# design.net
KiCad netlist of a schematic drawn in Altium Designer
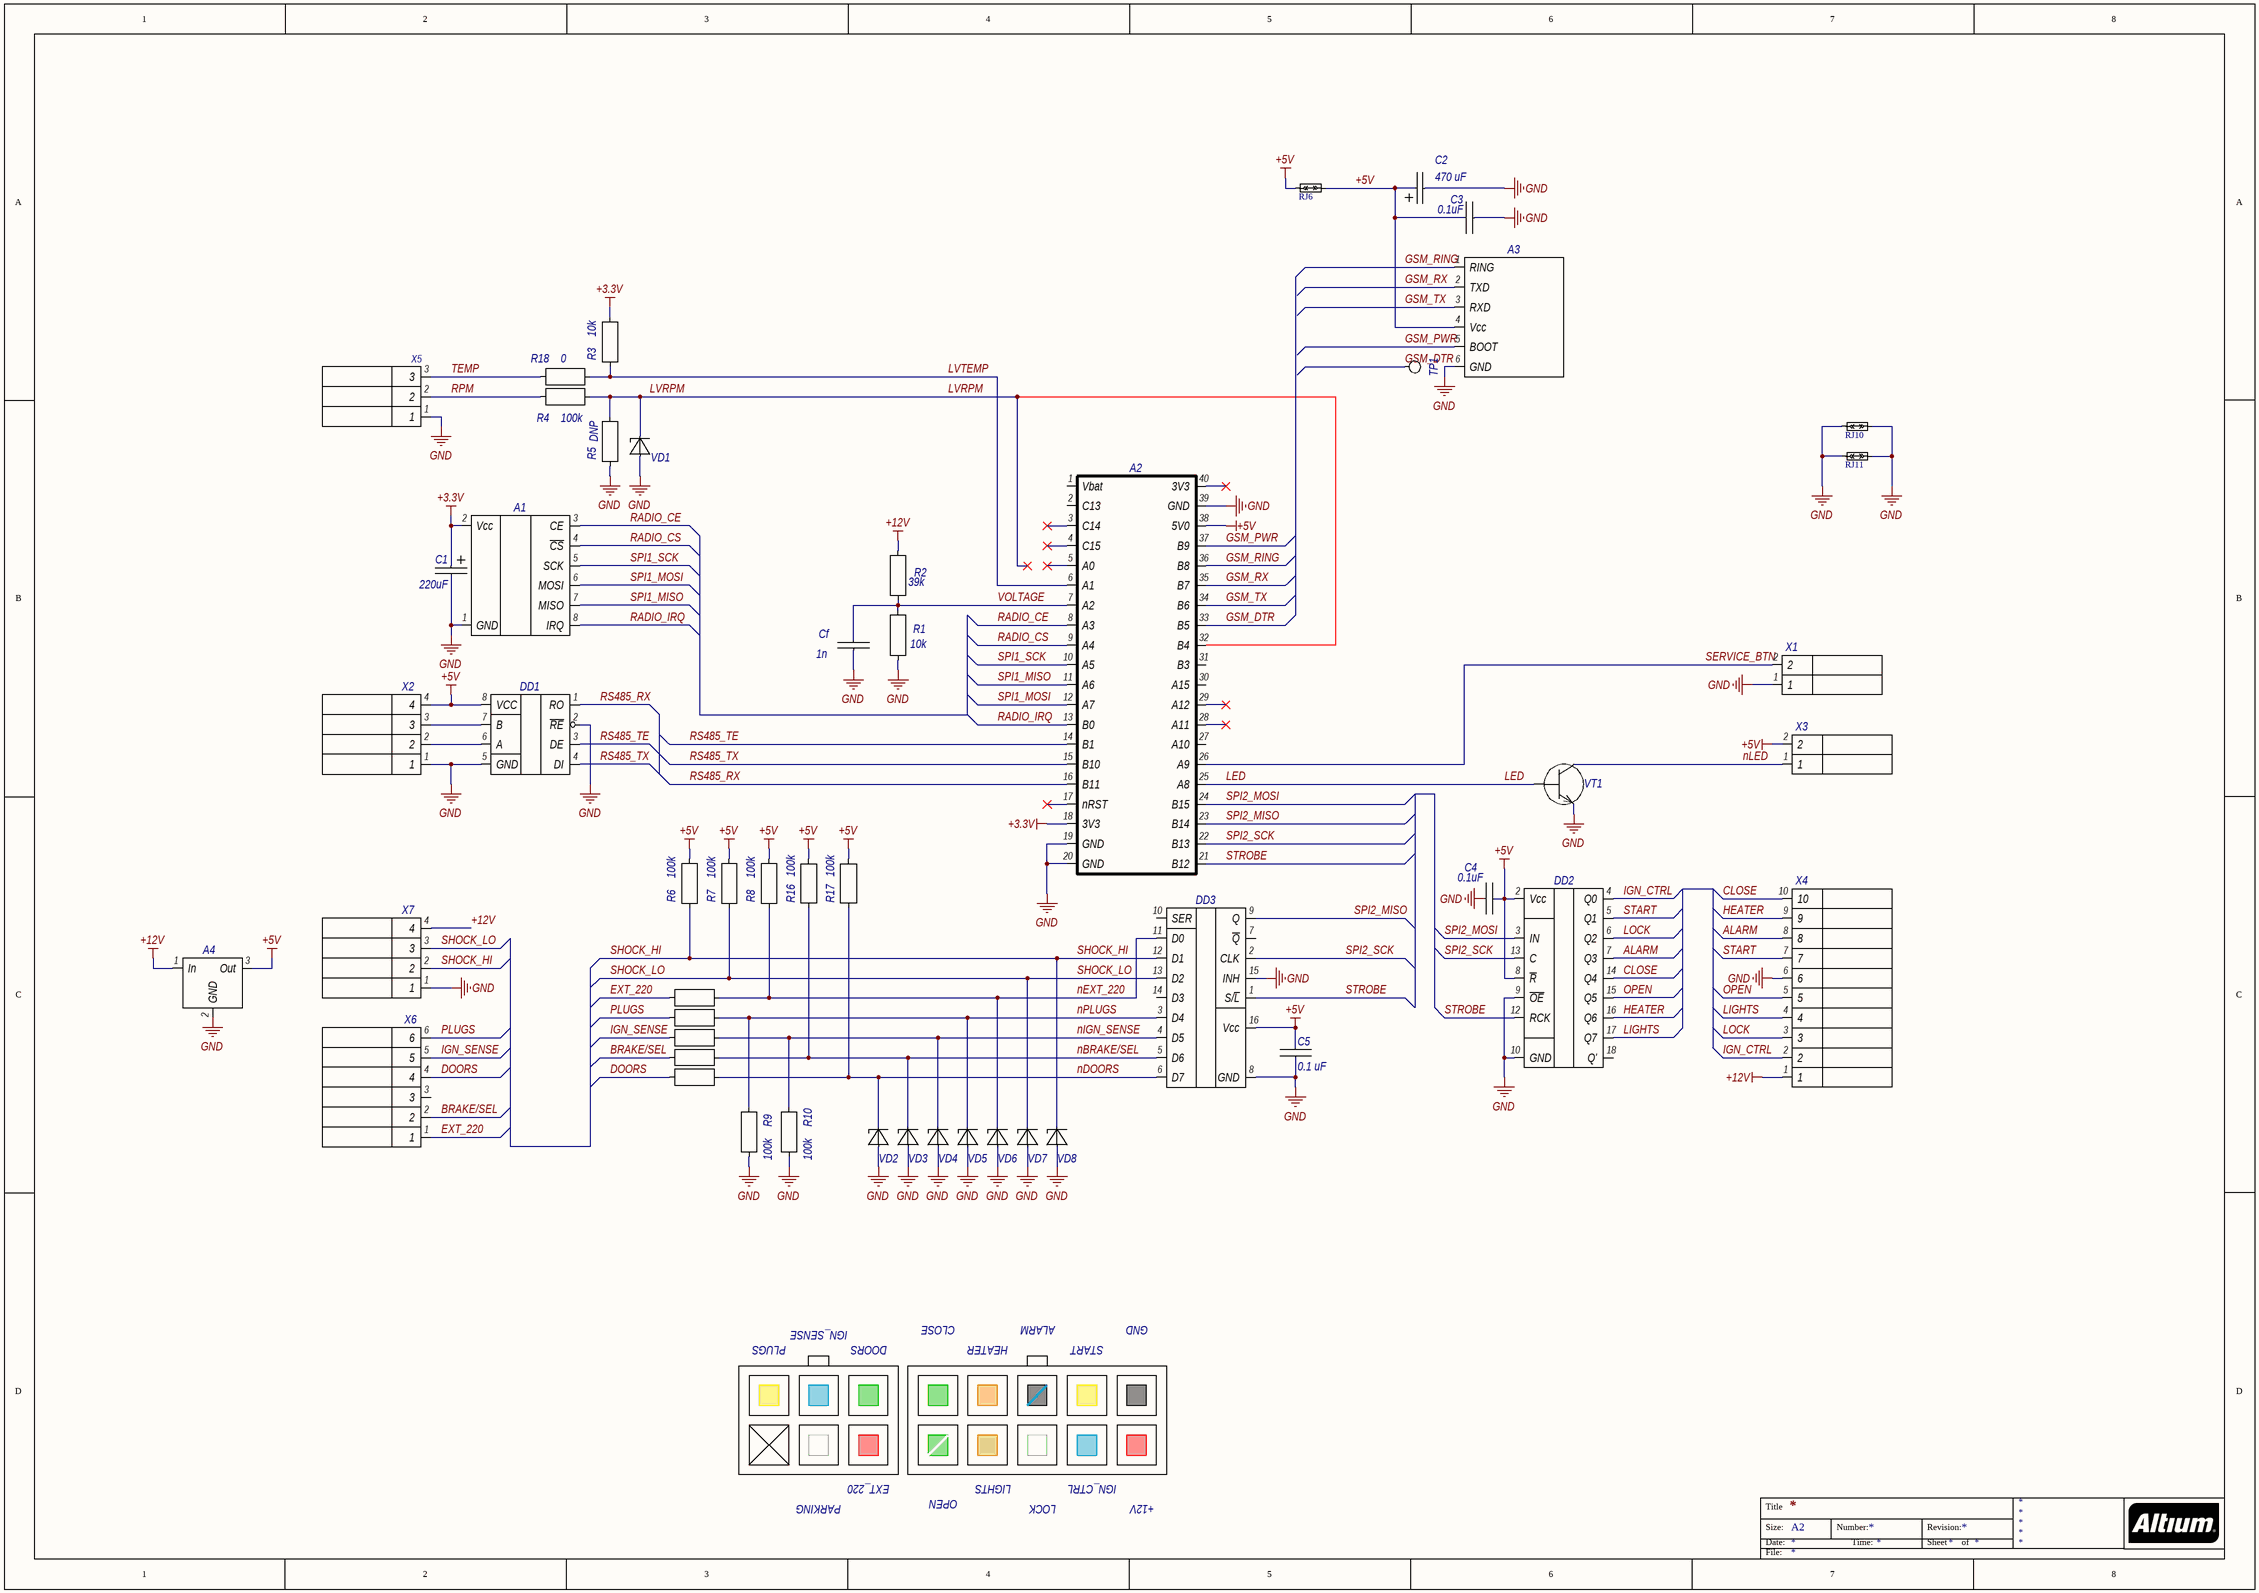
[diagram p0: Основной блок.SchDoc]

(export (version "E")
  (design (tool "Eeschema 10.0.6"))
  (components
    (comp (ref "A1")
      (value "nRF24L01 + PA + LNA")
      (footprint "nRF24L01+PA+LNA Thruhole")
      (description "=PartNumber")
      (fields (field (name "PARTNUMBER") "nRF24L01+PA+LNA Module"))
      (libsource (lib "modules") (part "nRF24L01 + PA + LNA"))
    )
    (comp (ref "A2")
      (value "STM32-1")
      (footprint "STM32 Module No. 1")
      (description "=PartNumber")
      (fields (field (name "PARTNUMBER") "STM32F103 \"Blue Pill\" Module"))
      (libsource (lib "modules") (part "STM32-1"))
    )
    (comp (ref "A3")
      (value "M590E Сборка")
      (footprint "M590E_Module_1")
      (description "=PartNumber")
      (fields (field (name "PARTNUMBER") "Neoway M590 Assy"))
      (libsource (lib "modules") (part "M590E Сборка"))
    )
    (comp (ref "A4")
      (value "LM2596 Module")
      (footprint "LM2596 Module")
      (description "=PartNumber")
      (fields (field (name "PARTNUMBER") "DC-DC Converter Module"))
      (libsource (lib "modules") (part "LM2596 Module"))
    )
    (comp (ref "C1")
      (value "220uF")
      (footprint "CAP_TYPE_C")
      (description "=PartNumber")
      (fields (field (name "PARTNUMBER") "T491C227K006AT") (field (name "Comment") "Конденсатор"))
      (libsource (lib "RCL") (part "Конденсатор"))
    )
    (comp (ref "C2")
      (value "470 uF")
      (footprint "CAP_TYPE_D")
      (description "=PartNumber")
      (fields (field (name "PARTNUMBER") "T491D477K006AT") (field (name "Comment") "Конденсатор"))
      (libsource (lib "RCL") (part "Конденсатор"))
    )
    (comp (ref "C3")
      (value "0.1uF")
      (footprint "CHIP_0603_C")
      (description "=PartNumber")
      (fields (field (name "PARTNUMBER") "CC0603KRX7R7BB104") (field (name "Comment") "Конденсатор"))
      (libsource (lib "") (part "Конденсатор_1"))
    )
    (comp (ref "C4")
      (value "0.1uF")
      (footprint "CHIP_0603_C")
      (description "=PartNumber")
      (fields (field (name "PARTNUMBER") "CC0603KRX7R7BB104") (field (name "Comment") "Конденсатор"))
      (libsource (lib "") (part "Конденсатор_1"))
    )
    (comp (ref "C5")
      (value "0.1 uF")
      (footprint "CHIP_1206_C")
      (description "=PartNumber")
      (fields (field (name "PARTNUMBER") "CC1206KRX7R9BB104") (field (name "Comment") "Конденсатор"))
      (libsource (lib "") (part "Конденсатор_1"))
    )
    (comp (ref "Cf")
      (value "1n")
      (footprint "CHIP_0603_C")
      (description "=PartNumber")
      (fields (field (name "PARTNUMBER") "CC0603KRX7R7BB104") (field (name "Comment") "Конденсатор"))
      (libsource (lib "") (part "Конденсатор_1"))
    )
    (comp (ref "DD1")
      (value "ADM485AR")
      (footprint "SO8")
      (description "=PartNumber")
      (fields (field (name "PARTNUMBER") "ADM485ARZ-REEL"))
      (libsource (lib "ic") (part "ADM485AR"))
    )
    (comp (ref "DD2")
      (value "TPIC6B595")
      (footprint "SO20W - TPIC6B595")
      (description "=PartNumber")
      (fields (field (name "PARTNUMBER") "TPIC6B595DW (SO20W)"))
      (libsource (lib "ic") (part "TPIC6B595"))
    )
    (comp (ref "DD3")
      (value "74HC165")
      (footprint "DIP16")
      (description "=PartNumber")
      (fields (field (name "PARTNUMBER") "SN74HC165N  (DIP16)"))
      (libsource (lib "ic") (part "74HC165"))
    )
    (comp (ref "R1")
      (value "10k")
      (footprint "CHIP_0603_R")
      (description "=PartNumber")
      (fields (field (name "Comment") "Резистор"))
      (libsource (lib "RCL") (part "Резистор"))
    )
    (comp (ref "R2")
      (value "39k")
      (footprint "R_0.125 - 400mil")
      (description "=PartNumber")
      (fields (field (name "Comment") "Резистор"))
      (libsource (lib "RCL") (part "Резистор"))
    )
    (comp (ref "R3")
      (value "10k")
      (footprint "CHIP_0603_R")
      (description "=PartNumber")
      (fields (field (name "Comment") "Резистор"))
      (libsource (lib "RCL") (part "Резистор"))
    )
    (comp (ref "R4")
      (value "100k")
      (footprint "CHIP_1206_R")
      (description "=PartNumber")
      (fields (field (name "Comment") "Резистор"))
      (libsource (lib "RCL") (part "Резистор"))
    )
    (comp (ref "R5")
      (value "DNP")
      (footprint "CHIP_0603_R")
      (description "=PartNumber")
      (fields (field (name "Comment") "Резистор"))
      (libsource (lib "RCL") (part "Резистор"))
    )
    (comp (ref "R6")
      (value "100k")
      (footprint "CHIP_1206_R")
      (description "=PartNumber")
      (fields (field (name "PARTNUMBER") "RC1206FR-07100KL") (field (name "Comment") "Резистор"))
      (libsource (lib "RCL") (part "Резистор"))
    )
    (comp (ref "R7")
      (value "100k")
      (footprint "CHIP_1206_R")
      (description "=PartNumber")
      (fields (field (name "PARTNUMBER") "RC1206FR-07100KL") (field (name "Comment") "Резистор"))
      (libsource (lib "RCL") (part "Резистор"))
    )
    (comp (ref "R8")
      (value "100k")
      (footprint "CHIP_1206_R")
      (description "=PartNumber")
      (fields (field (name "PARTNUMBER") "RC1206FR-07100KL") (field (name "Comment") "Резистор"))
      (libsource (lib "RCL") (part "Резистор"))
    )
    (comp (ref "R9")
      (value "100k")
      (footprint "CHIP_1206_R")
      (description "=PartNumber")
      (fields (field (name "PARTNUMBER") "RC1206FR-07100KL") (field (name "Comment") "Резистор"))
      (libsource (lib "RCL") (part "Резистор"))
    )
    (comp (ref "R10")
      (value "100k")
      (footprint "CHIP_1206_R")
      (description "=PartNumber")
      (fields (field (name "PARTNUMBER") "RC1206FR-07100KL") (field (name "Comment") "Резистор"))
      (libsource (lib "RCL") (part "Резистор"))
    )
    (comp (ref "R11")
      (value "Резистор")
      (footprint "R_0.125 - 400mil")
      (description "=PartNumber")
      (libsource (lib "RCL") (part "Резистор"))
    )
    (comp (ref "R12")
      (value "Резистор")
      (footprint "R_0.125 - 400mil")
      (description "=PartNumber")
      (libsource (lib "RCL") (part "Резистор"))
    )
    (comp (ref "R13")
      (value "Резистор")
      (footprint "R_0.125 - 400mil")
      (description "=PartNumber")
      (libsource (lib "RCL") (part "Резистор"))
    )
    (comp (ref "R14")
      (value "Резистор")
      (footprint "R_0.125 - 400mil")
      (description "=PartNumber")
      (libsource (lib "RCL") (part "Резистор"))
    )
    (comp (ref "R15")
      (value "Резистор")
      (footprint "R_0.125 - 400mil")
      (description "=PartNumber")
      (libsource (lib "RCL") (part "Резистор"))
    )
    (comp (ref "R16")
      (value "100k")
      (footprint "CHIP_1206_R")
      (description "=PartNumber")
      (fields (field (name "PARTNUMBER") "RC1206FR-07100KL") (field (name "Comment") "Резистор"))
      (libsource (lib "RCL") (part "Резистор"))
    )
    (comp (ref "R17")
      (value "100k")
      (footprint "CHIP_1206_R")
      (description "=PartNumber")
      (fields (field (name "PARTNUMBER") "RC1206FR-07100KL") (field (name "Comment") "Резистор"))
      (libsource (lib "RCL") (part "Резистор"))
    )
    (comp (ref "R18")
      (value "0")
      (footprint "CHIP_1206_R")
      (description "=PartNumber")
      (fields (field (name "Comment") "Резистор"))
      (libsource (lib "RCL") (part "Резистор"))
    )
    (comp (ref "RJ6")
      (value "R0")
      (footprint "CHIP_1206_R0")
      (description "=PartNumber")
      (fields (field (name "PARTNUMBER") "RC1206JR-070RL"))
      (libsource (lib "passive") (part "R0"))
    )
    (comp (ref "RJ10")
      (value "R0")
      (footprint "CHIP_1206_R0")
      (description "=PartNumber")
      (fields (field (name "PARTNUMBER") "RC1206JR-070RL"))
      (libsource (lib "passive") (part "R0"))
    )
    (comp (ref "RJ11")
      (value "R0")
      (footprint "CHIP_1206_R0")
      (description "=PartNumber")
      (fields (field (name "PARTNUMBER") "RC1206JR-070RL"))
      (libsource (lib "passive") (part "R0"))
    )
    (comp (ref "TP1")
      (value "TEST_POINT")
      (footprint "Mounting hole 1.5mm")
      (libsource (lib "conn") (part "TEST_POINT"))
    )
    (comp (ref "VD1")
      (value "Zener")
      (footprint "SOD-80")
      (description "=PartNumber")
      (fields (field (name "PARTNUMBER") "ZMM5226B (ZMM55C-3V3)"))
      (libsource (lib "Semiconductors") (part "Zener"))
    )
    (comp (ref "VD2")
      (value "Zener")
      (footprint "SOD-80")
      (description "=PartNumber")
      (fields (field (name "PARTNUMBER") "ZMM5229B (ZMM55C-4V3)"))
      (libsource (lib "Semiconductors") (part "Zener"))
    )
    (comp (ref "VD3")
      (value "Zener")
      (footprint "SOD-80")
      (description "=PartNumber")
      (fields (field (name "PARTNUMBER") "ZMM5229B (ZMM55C-4V3)"))
      (libsource (lib "Semiconductors") (part "Zener"))
    )
    (comp (ref "VD4")
      (value "Zener")
      (footprint "SOD-80")
      (description "=PartNumber")
      (fields (field (name "PARTNUMBER") "ZMM5229B (ZMM55C-4V3)"))
      (libsource (lib "Semiconductors") (part "Zener"))
    )
    (comp (ref "VD5")
      (value "Zener")
      (footprint "SOD-80")
      (description "=PartNumber")
      (fields (field (name "PARTNUMBER") "ZMM5229B (ZMM55C-4V3)"))
      (libsource (lib "Semiconductors") (part "Zener"))
    )
    (comp (ref "VD6")
      (value "Zener")
      (footprint "SOD-80")
      (description "=PartNumber")
      (fields (field (name "PARTNUMBER") "ZMM5229B (ZMM55C-4V3)"))
      (libsource (lib "Semiconductors") (part "Zener"))
    )
    (comp (ref "VD7")
      (value "Zener")
      (footprint "SOD-80")
      (description "=PartNumber")
      (fields (field (name "PARTNUMBER") "ZMM5229B (ZMM55C-4V3)"))
      (libsource (lib "Semiconductors") (part "Zener"))
    )
    (comp (ref "VD8")
      (value "Zener")
      (footprint "SOD-80")
      (description "=PartNumber")
      (fields (field (name "PARTNUMBER") "ZMM5229B (ZMM55C-4V3)"))
      (libsource (lib "Semiconductors") (part "Zener"))
    )
    (comp (ref "VT1")
      (value "BJT, NPN")
      (footprint "SOT-23")
      (description "=PartNumber")
      (fields (field (name "PARTNUMBER") "KSR1002") (field (name "MFG") "SAM"))
      (libsource (lib "Semiconductors") (part "BJT, NPN"))
    )
    (comp (ref "X1")
      (value "PH-02M(R)")
      (footprint "PH-02MR")
      (description "=PartNumber")
      (fields (field (name "PARTNUMBER") "PH 02MR 2.0mm"))
      (libsource (lib "conn") (part "PH-02M(R)"))
    )
    (comp (ref "X2")
      (value "PH-04M(R)")
      (footprint "PH-04M")
      (description "=PartNumber")
      (fields (field (name "PARTNUMBER") "PH 02M 2.0mm"))
      (libsource (lib "conn") (part "PH-04M(R)"))
    )
    (comp (ref "X3")
      (value "PH-02M(R)")
      (footprint "PH-02MR")
      (description "=PartNumber")
      (fields (field (name "PARTNUMBER") "PH 02MR 2.0mm"))
      (libsource (lib "conn") (part "PH-02M(R)"))
    )
    (comp (ref "X4")
      (value "MF 2x05 M(R)")
      (footprint "MF 2x05 R")
      (description "=PartNumber")
      (fields (field (name "PARTNUMBER") "MF 2x05MR"))
      (libsource (lib "conn") (part "MF 2x05 M(R)"))
    )
    (comp (ref "X5")
      (value "PH-03M(R)")
      (footprint "PH-03M")
      (description "=PartNumber")
      (fields (field (name "PARTNUMBER") "PH 02M 2.0mm"))
      (libsource (lib "conn") (part "PH-03M(R)"))
    )
    (comp (ref "X6")
      (value "MF 2x03 M(R)")
      (footprint "MF 2x03 R")
      (description "=PartNumber")
      (fields (field (name "PARTNUMBER") "MF 2x03MR"))
      (libsource (lib "conn") (part "MF 2x03 M(R)"))
    )
    (comp (ref "X7")
      (value "PH-04M(R)")
      (footprint "PH-04MR")
      (description "=PartNumber")
      (fields (field (name "PARTNUMBER") "PH 04MR 2.0mm"))
      (libsource (lib "conn") (part "PH-04M(R)"))
    )
  )
  (nets
    (net (code "1") (name "+3.3V") (class "Default")
      (node (ref "A1") (pin "2") (pinfunction "Vcc_2") (pintype "passive"))
      (node (ref "A2") (pin "18") (pinfunction "3V3_18") (pintype "passive"))
      (node (ref "C1") (pin "2") (pinfunction "2_2") (pintype "passive"))
      (node (ref "R3") (pin "2") (pinfunction "2_2") (pintype "passive"))
    )
    (net (code "2") (name "+5V") (class "Default")
      (node (ref "A2") (pin "38") (pinfunction "5V0_38") (pintype "passive"))
      (node (ref "A3") (pin "4") (pinfunction "Vcc_4") (pintype "passive"))
      (node (ref "A4") (pin "3") (pinfunction "Out_3") (pintype "passive"))
      (node (ref "C2") (pin "2") (pinfunction "2_2") (pintype "passive"))
      (node (ref "C3") (pin "1") (pinfunction "1_1") (pintype "passive"))
      (node (ref "C4") (pin "1") (pinfunction "1_1") (pintype "passive"))
      (node (ref "C5") (pin "2") (pinfunction "2_2") (pintype "passive"))
      (node (ref "DD1") (pin "8") (pinfunction "VCC_8") (pintype "passive"))
      (node (ref "DD2") (pin "2") (pinfunction "Vcc_2") (pintype "passive"))
      (node (ref "DD2") (pin "8") (pinfunction "R_8") (pintype "passive"))
      (node (ref "DD3") (pin "16") (pinfunction "Vcc_16") (pintype "passive"))
      (node (ref "R16") (pin "1") (pinfunction "1_1") (pintype "passive"))
      (node (ref "R17") (pin "1") (pinfunction "1_1") (pintype "passive"))
      (node (ref "R6") (pin "2") (pinfunction "2_2") (pintype "passive"))
      (node (ref "R7") (pin "2") (pinfunction "2_2") (pintype "passive"))
      (node (ref "R8") (pin "2") (pinfunction "2_2") (pintype "passive"))
      (node (ref "RJ6") (pin "1") (pinfunction "1_1") (pintype "passive"))
      (node (ref "RJ6") (pin "2") (pinfunction "2_2") (pintype "passive"))
      (node (ref "X2") (pin "4") (pinfunction "4_4") (pintype "passive"))
      (node (ref "X3") (pin "2") (pinfunction "2_2") (pintype "passive"))
    )
    (net (code "3") (name "+12V") (class "Default")
      (node (ref "A4") (pin "1") (pinfunction "In_1") (pintype "passive"))
      (node (ref "R2") (pin "2") (pinfunction "2_2") (pintype "passive"))
      (node (ref "X4") (pin "1") (pinfunction "1_1") (pintype "passive"))
      (node (ref "X7") (pin "4") (pinfunction "4_4") (pintype "passive"))
    )
    (net (code "4") (name "/ALARM") (class "Default")
      (node (ref "DD2") (pin "7") (pinfunction "Q3_7") (pintype "passive"))
      (node (ref "X4") (pin "8") (pinfunction "8_8") (pintype "passive"))
    )
    (net (code "5") (name "/BRAKE{slash}SEL") (class "Default")
      (node (ref "R14") (pin "1") (pinfunction "1_1") (pintype "passive"))
      (node (ref "X6") (pin "2") (pinfunction "2_2") (pintype "passive"))
    )
    (net (code "6") (name "/CLOSE") (class "Default")
      (node (ref "DD2") (pin "14") (pinfunction "Q4_14") (pintype "passive"))
      (node (ref "X4") (pin "10") (pinfunction "10_10") (pintype "passive"))
    )
    (net (code "7") (name "/DOORS") (class "Default")
      (node (ref "R15") (pin "1") (pinfunction "1_1") (pintype "passive"))
      (node (ref "X6") (pin "4") (pinfunction "4_4") (pintype "passive"))
    )
    (net (code "8") (name "/EXT_220") (class "Default")
      (node (ref "R11") (pin "1") (pinfunction "1_1") (pintype "passive"))
      (node (ref "X6") (pin "1") (pinfunction "1_1") (pintype "passive"))
    )
    (net (code "9") (name "/GSM_DTR") (class "Default")
      (node (ref "A2") (pin "33") (pinfunction "B5_33") (pintype "passive"))
      (node (ref "TP1") (pin "1") (pintype "passive"))
    )
    (net (code "10") (name "/GSM_PWR") (class "Default")
      (node (ref "A2") (pin "37") (pinfunction "B9_37") (pintype "passive"))
      (node (ref "A3") (pin "5") (pinfunction "BOOT_5") (pintype "passive"))
    )
    (net (code "11") (name "/GSM_RING") (class "Default")
      (node (ref "A2") (pin "36") (pinfunction "B8_36") (pintype "passive"))
      (node (ref "A3") (pin "1") (pinfunction "RING_1") (pintype "passive"))
    )
    (net (code "12") (name "/GSM_RX") (class "Default")
      (node (ref "A2") (pin "35") (pinfunction "B7_35") (pintype "passive"))
      (node (ref "A3") (pin "2") (pinfunction "TXD_2") (pintype "passive"))
    )
    (net (code "13") (name "/GSM_TX") (class "Default")
      (node (ref "A2") (pin "34") (pinfunction "B6_34") (pintype "passive"))
      (node (ref "A3") (pin "3") (pinfunction "RXD_3") (pintype "passive"))
    )
    (net (code "14") (name "/HEATER") (class "Default")
      (node (ref "DD2") (pin "16") (pinfunction "Q6_16") (pintype "passive"))
      (node (ref "X4") (pin "9") (pinfunction "9_9") (pintype "passive"))
    )
    (net (code "15") (name "/IGN_CTRL") (class "Default")
      (node (ref "DD2") (pin "4") (pinfunction "Q0_4") (pintype "passive"))
      (node (ref "X4") (pin "2") (pinfunction "2_2") (pintype "passive"))
    )
    (net (code "16") (name "/IGN_SENSE") (class "Default")
      (node (ref "R13") (pin "1") (pinfunction "1_1") (pintype "passive"))
      (node (ref "X6") (pin "5") (pinfunction "5_5") (pintype "passive"))
    )
    (net (code "17") (name "/LED") (class "Default")
      (node (ref "A2") (pin "25") (pinfunction "A8_25") (pintype "passive"))
      (node (ref "VT1") (pin "1") (pinfunction "1_1") (pintype "passive"))
    )
    (net (code "18") (name "/LIGHTS") (class "Default")
      (node (ref "DD2") (pin "17") (pinfunction "Q7_17") (pintype "passive"))
      (node (ref "X4") (pin "4") (pinfunction "4_4") (pintype "passive"))
    )
    (net (code "19") (name "/LOCK") (class "Default")
      (node (ref "DD2") (pin "6") (pinfunction "Q2_6") (pintype "passive"))
      (node (ref "X4") (pin "3") (pinfunction "3_3") (pintype "passive"))
    )
    (net (code "20") (name "/LVRPM") (class "Default")
      (node (ref "A2") (pin "32") (pinfunction "B4_32") (pintype "passive"))
      (node (ref "R4") (pin "2") (pinfunction "2_2") (pintype "passive"))
      (node (ref "R5") (pin "2") (pinfunction "2_2") (pintype "passive"))
      (node (ref "VD1") (pin "2") (pinfunction "2_2") (pintype "passive"))
    )
    (net (code "21") (name "/LVTEMP") (class "Default")
      (node (ref "A2") (pin "6") (pinfunction "A1_6") (pintype "passive"))
      (node (ref "R18") (pin "2") (pinfunction "2_2") (pintype "passive"))
      (node (ref "R3") (pin "1") (pinfunction "1_1") (pintype "passive"))
    )
    (net (code "22") (name "/OPEN") (class "Default")
      (node (ref "DD2") (pin "15") (pinfunction "Q5_15") (pintype "passive"))
      (node (ref "X4") (pin "5") (pinfunction "5_5") (pintype "passive"))
    )
    (net (code "23") (name "/PLUGS") (class "Default")
      (node (ref "R12") (pin "1") (pinfunction "1_1") (pintype "passive"))
      (node (ref "X6") (pin "6") (pinfunction "6_6") (pintype "passive"))
    )
    (net (code "24") (name "/RADIO_CE") (class "Default")
      (node (ref "A1") (pin "3") (pinfunction "CE_3") (pintype "passive"))
      (node (ref "A2") (pin "8") (pinfunction "A3_8") (pintype "passive"))
    )
    (net (code "25") (name "/RADIO_CS") (class "Default")
      (node (ref "A1") (pin "4") (pinfunction "CS_4") (pintype "passive"))
      (node (ref "A2") (pin "9") (pinfunction "A4_9") (pintype "passive"))
    )
    (net (code "26") (name "/RADIO_IRQ") (class "Default")
      (node (ref "A1") (pin "8") (pinfunction "IRQ_8") (pintype "passive"))
      (node (ref "A2") (pin "13") (pinfunction "B0_13") (pintype "passive"))
    )
    (net (code "27") (name "/RPM") (class "Default")
      (node (ref "R4") (pin "1") (pinfunction "1_1") (pintype "passive"))
      (node (ref "X5") (pin "2") (pinfunction "2_2") (pintype "passive"))
    )
    (net (code "28") (name "/RS485_RX") (class "Default")
      (node (ref "A2") (pin "16") (pinfunction "B11_16") (pintype "passive"))
      (node (ref "DD1") (pin "1") (pinfunction "RO_1") (pintype "passive"))
    )
    (net (code "29") (name "/RS485_TE") (class "Default")
      (node (ref "A2") (pin "14") (pinfunction "B1_14") (pintype "passive"))
      (node (ref "DD1") (pin "3") (pinfunction "DE_3") (pintype "passive"))
    )
    (net (code "30") (name "/RS485_TX") (class "Default")
      (node (ref "A2") (pin "15") (pinfunction "B10_15") (pintype "passive"))
      (node (ref "DD1") (pin "4") (pinfunction "DI_4") (pintype "passive"))
    )
    (net (code "31") (name "/SERVICE_BTN") (class "Default")
      (node (ref "A2") (pin "26") (pinfunction "A9_26") (pintype "passive"))
      (node (ref "X1") (pin "2") (pinfunction "2_2") (pintype "passive"))
    )
    (net (code "32") (name "/SHOCK_HI") (class "Default")
      (node (ref "DD3") (pin "12") (pinfunction "D1_12") (pintype "passive"))
      (node (ref "R6") (pin "1") (pinfunction "1_1") (pintype "passive"))
      (node (ref "VD8") (pin "2") (pinfunction "2_2") (pintype "passive"))
      (node (ref "X7") (pin "2") (pinfunction "2_2") (pintype "passive"))
    )
    (net (code "33") (name "/SHOCK_LO") (class "Default")
      (node (ref "DD3") (pin "13") (pinfunction "D2_13") (pintype "passive"))
      (node (ref "R7") (pin "1") (pinfunction "1_1") (pintype "passive"))
      (node (ref "VD7") (pin "2") (pinfunction "2_2") (pintype "passive"))
      (node (ref "X7") (pin "3") (pinfunction "3_3") (pintype "passive"))
    )
    (net (code "34") (name "/SPI1_MISO") (class "Default")
      (node (ref "A1") (pin "7") (pinfunction "MISO_7") (pintype "passive"))
      (node (ref "A2") (pin "11") (pinfunction "A6_11") (pintype "passive"))
    )
    (net (code "35") (name "/SPI1_MOSI") (class "Default")
      (node (ref "A1") (pin "6") (pinfunction "MOSI_6") (pintype "passive"))
      (node (ref "A2") (pin "12") (pinfunction "A7_12") (pintype "passive"))
    )
    (net (code "36") (name "/SPI1_SCK") (class "Default")
      (node (ref "A1") (pin "5") (pinfunction "SCK_5") (pintype "passive"))
      (node (ref "A2") (pin "10") (pinfunction "A5_10") (pintype "passive"))
    )
    (net (code "37") (name "/SPI2_MISO") (class "Default")
      (node (ref "A2") (pin "23") (pinfunction "B14_23") (pintype "passive"))
      (node (ref "DD3") (pin "9") (pinfunction "Q_9") (pintype "passive"))
    )
    (net (code "38") (name "/SPI2_MOSI") (class "Default")
      (node (ref "A2") (pin "24") (pinfunction "B15_24") (pintype "passive"))
      (node (ref "DD2") (pin "3") (pinfunction "IN_3") (pintype "passive"))
    )
    (net (code "39") (name "/SPI2_SCK") (class "Default")
      (node (ref "A2") (pin "22") (pinfunction "B13_22") (pintype "passive"))
      (node (ref "DD2") (pin "13") (pinfunction "C_13") (pintype "passive"))
      (node (ref "DD3") (pin "2") (pinfunction "CLK_2") (pintype "passive"))
    )
    (net (code "40") (name "/START") (class "Default")
      (node (ref "DD2") (pin "5") (pinfunction "Q1_5") (pintype "passive"))
      (node (ref "X4") (pin "7") (pinfunction "7_7") (pintype "passive"))
    )
    (net (code "41") (name "/STROBE") (class "Default")
      (node (ref "A2") (pin "21") (pinfunction "B12_21") (pintype "passive"))
      (node (ref "DD2") (pin "12") (pinfunction "RCK_12") (pintype "passive"))
      (node (ref "DD3") (pin "1") (pinfunction "S/~{L}_1") (pintype "passive"))
    )
    (net (code "42") (name "/TEMP") (class "Default")
      (node (ref "R18") (pin "1") (pinfunction "1_1") (pintype "passive"))
      (node (ref "X5") (pin "3") (pinfunction "3_3") (pintype "passive"))
    )
    (net (code "43") (name "/VOLTAGE") (class "Default")
      (node (ref "A2") (pin "7") (pinfunction "A2_7") (pintype "passive"))
      (node (ref "Cf") (pin "1") (pinfunction "1_1") (pintype "passive"))
      (node (ref "R1") (pin "2") (pinfunction "2_2") (pintype "passive"))
      (node (ref "R2") (pin "1") (pinfunction "1_1") (pintype "passive"))
    )
    (net (code "44") (name "/nBRAKE{slash}SEL") (class "Default")
      (node (ref "DD3") (pin "5") (pinfunction "D6_5") (pintype "passive"))
      (node (ref "R14") (pin "2") (pinfunction "2_2") (pintype "passive"))
      (node (ref "R16") (pin "2") (pinfunction "2_2") (pintype "passive"))
      (node (ref "VD3") (pin "2") (pinfunction "2_2") (pintype "passive"))
    )
    (net (code "45") (name "/nDOORS") (class "Default")
      (node (ref "DD3") (pin "6") (pinfunction "D7_6") (pintype "passive"))
      (node (ref "R15") (pin "2") (pinfunction "2_2") (pintype "passive"))
      (node (ref "R17") (pin "2") (pinfunction "2_2") (pintype "passive"))
      (node (ref "VD2") (pin "2") (pinfunction "2_2") (pintype "passive"))
    )
    (net (code "46") (name "/nEXT_220") (class "Default")
      (node (ref "DD3") (pin "11") (pinfunction "D0_11") (pintype "passive"))
      (node (ref "R11") (pin "2") (pinfunction "2_2") (pintype "passive"))
      (node (ref "R8") (pin "1") (pinfunction "1_1") (pintype "passive"))
      (node (ref "VD6") (pin "2") (pinfunction "2_2") (pintype "passive"))
    )
    (net (code "47") (name "/nIGN_SENSE") (class "Default")
      (node (ref "DD3") (pin "4") (pinfunction "D5_4") (pintype "passive"))
      (node (ref "R10") (pin "1") (pinfunction "1_1") (pintype "passive"))
      (node (ref "R13") (pin "2") (pinfunction "2_2") (pintype "passive"))
      (node (ref "VD4") (pin "2") (pinfunction "2_2") (pintype "passive"))
    )
    (net (code "48") (name "/nLED") (class "Default")
      (node (ref "VT1") (pin "2") (pinfunction "2_2") (pintype "passive"))
      (node (ref "X3") (pin "1") (pinfunction "1_1") (pintype "passive"))
    )
    (net (code "49") (name "/nPLUGS") (class "Default")
      (node (ref "DD3") (pin "3") (pinfunction "D4_3") (pintype "passive"))
      (node (ref "R12") (pin "2") (pinfunction "2_2") (pintype "passive"))
      (node (ref "R9") (pin "1") (pinfunction "1_1") (pintype "passive"))
      (node (ref "VD5") (pin "2") (pinfunction "2_2") (pintype "passive"))
    )
    (net (code "50") (name "GND") (class "Default")
      (node (ref "A1") (pin "1") (pinfunction "GND_1") (pintype "passive"))
      (node (ref "A2") (pin "19") (pinfunction "GND_19") (pintype "passive"))
      (node (ref "A2") (pin "20") (pinfunction "GND_20") (pintype "passive"))
      (node (ref "A2") (pin "39") (pinfunction "GND_39") (pintype "passive"))
      (node (ref "A3") (pin "6") (pinfunction "GND_6") (pintype "passive"))
      (node (ref "A4") (pin "2") (pinfunction "GND_2") (pintype "passive"))
      (node (ref "C1") (pin "1") (pinfunction "1_1") (pintype "passive"))
      (node (ref "C2") (pin "1") (pinfunction "1_1") (pintype "passive"))
      (node (ref "C3") (pin "2") (pinfunction "2_2") (pintype "passive"))
      (node (ref "C4") (pin "2") (pinfunction "2_2") (pintype "passive"))
      (node (ref "C5") (pin "1") (pinfunction "1_1") (pintype "passive"))
      (node (ref "Cf") (pin "2") (pinfunction "2_2") (pintype "passive"))
      (node (ref "DD1") (pin "2") (pinfunction "~{RE}_2") (pintype "passive"))
      (node (ref "DD1") (pin "5") (pinfunction "GND_5") (pintype "passive"))
      (node (ref "DD2") (pin "10") (pinfunction "GND_10") (pintype "passive"))
      (node (ref "DD2") (pin "9") (pinfunction "OE_9") (pintype "passive"))
      (node (ref "DD3") (pin "15") (pinfunction "INH_15") (pintype "passive"))
      (node (ref "DD3") (pin "8") (pinfunction "GND_8") (pintype "passive"))
      (node (ref "R1") (pin "1") (pinfunction "1_1") (pintype "passive"))
      (node (ref "R10") (pin "2") (pinfunction "2_2") (pintype "passive"))
      (node (ref "R5") (pin "1") (pinfunction "1_1") (pintype "passive"))
      (node (ref "R9") (pin "2") (pinfunction "2_2") (pintype "passive"))
      (node (ref "RJ10") (pin "1") (pinfunction "1_1") (pintype "passive"))
      (node (ref "RJ10") (pin "2") (pinfunction "2_2") (pintype "passive"))
      (node (ref "RJ11") (pin "1") (pinfunction "1_1") (pintype "passive"))
      (node (ref "RJ11") (pin "2") (pinfunction "2_2") (pintype "passive"))
      (node (ref "VD1") (pin "1") (pinfunction "1_1") (pintype "passive"))
      (node (ref "VD2") (pin "1") (pinfunction "1_1") (pintype "passive"))
      (node (ref "VD3") (pin "1") (pinfunction "1_1") (pintype "passive"))
      (node (ref "VD4") (pin "1") (pinfunction "1_1") (pintype "passive"))
      (node (ref "VD5") (pin "1") (pinfunction "1_1") (pintype "passive"))
      (node (ref "VD6") (pin "1") (pinfunction "1_1") (pintype "passive"))
      (node (ref "VD7") (pin "1") (pinfunction "1_1") (pintype "passive"))
      (node (ref "VD8") (pin "1") (pinfunction "1_1") (pintype "passive"))
      (node (ref "VT1") (pin "3") (pinfunction "3_3") (pintype "passive"))
      (node (ref "X1") (pin "1") (pinfunction "1_1") (pintype "passive"))
      (node (ref "X2") (pin "1") (pinfunction "1_1") (pintype "passive"))
      (node (ref "X4") (pin "6") (pinfunction "6_6") (pintype "passive"))
      (node (ref "X5") (pin "1") (pinfunction "1_1") (pintype "passive"))
      (node (ref "X7") (pin "1") (pinfunction "1_1") (pintype "passive"))
    )
    (net (code "51") (name "Net-(DD1-A)") (class "Default")
      (node (ref "DD1") (pin "6") (pinfunction "A_6") (pintype "passive"))
      (node (ref "X2") (pin "2") (pinfunction "2_2") (pintype "passive"))
    )
    (net (code "52") (name "Net-(DD1-B)") (class "Default")
      (node (ref "DD1") (pin "7") (pinfunction "B_7") (pintype "passive"))
      (node (ref "X2") (pin "3") (pinfunction "3_3") (pintype "passive"))
    )
    (net (code "53") (name "unconnected-(A2-3V3-Pad40)") (class "Default")
      (node (ref "A2") (pin "40") (pinfunction "3V3_40") (pintype "passive+no_connect"))
    )
    (net (code "54") (name "unconnected-(A2-A0-Pad5)") (class "Default")
      (node (ref "A2") (pin "5") (pinfunction "A0_5") (pintype "passive+no_connect"))
    )
    (net (code "55") (name "unconnected-(A2-A10-Pad27)") (class "Default")
      (node (ref "A2") (pin "27") (pinfunction "A10_27") (pintype "passive"))
    )
    (net (code "56") (name "unconnected-(A2-A11-Pad28)") (class "Default")
      (node (ref "A2") (pin "28") (pinfunction "A11_28") (pintype "passive+no_connect"))
    )
    (net (code "57") (name "unconnected-(A2-A12-Pad29)") (class "Default")
      (node (ref "A2") (pin "29") (pinfunction "A12_29") (pintype "passive+no_connect"))
    )
    (net (code "58") (name "unconnected-(A2-A15-Pad30)") (class "Default")
      (node (ref "A2") (pin "30") (pinfunction "A15_30") (pintype "passive"))
    )
    (net (code "59") (name "unconnected-(A2-B3-Pad31)") (class "Default")
      (node (ref "A2") (pin "31") (pinfunction "B3_31") (pintype "passive"))
    )
    (net (code "60") (name "unconnected-(A2-C13-Pad2)") (class "Default")
      (node (ref "A2") (pin "2") (pinfunction "C13_2") (pintype "passive"))
    )
    (net (code "61") (name "unconnected-(A2-C14-Pad3)") (class "Default")
      (node (ref "A2") (pin "3") (pinfunction "C14_3") (pintype "passive+no_connect"))
    )
    (net (code "62") (name "unconnected-(A2-C15-Pad4)") (class "Default")
      (node (ref "A2") (pin "4") (pinfunction "C15_4") (pintype "passive+no_connect"))
    )
    (net (code "63") (name "unconnected-(A2-Vbat-Pad1)") (class "Default")
      (node (ref "A2") (pin "1") (pinfunction "Vbat_1") (pintype "passive"))
    )
    (net (code "64") (name "unconnected-(A2-nRST-Pad17)") (class "Default")
      (node (ref "A2") (pin "17") (pinfunction "nRST_17") (pintype "passive+no_connect"))
    )
    (net (code "65") (name "unconnected-(DD2-Q'-Pad18)") (class "Default")
      (node (ref "DD2") (pin "18") (pinfunction "Q'_18") (pintype "passive"))
    )
    (net (code "66") (name "unconnected-(DD3-D3-Pad14)") (class "Default")
      (node (ref "DD3") (pin "14") (pinfunction "D3_14") (pintype "passive"))
    )
    (net (code "67") (name "unconnected-(DD3-Q-Pad7)") (class "Default")
      (node (ref "DD3") (pin "7") (pinfunction "Q_7") (pintype "passive"))
    )
    (net (code "68") (name "unconnected-(DD3-SER-Pad10)") (class "Default")
      (node (ref "DD3") (pin "10") (pinfunction "SER_10") (pintype "passive"))
    )
    (net (code "69") (name "unconnected-(X6-Pad3)") (class "Default")
      (node (ref "X6") (pin "3") (pinfunction "3_3") (pintype "passive"))
    )
  )
)
